# pilly.net
KiCad netlist of a schematic drawn in EAGLE
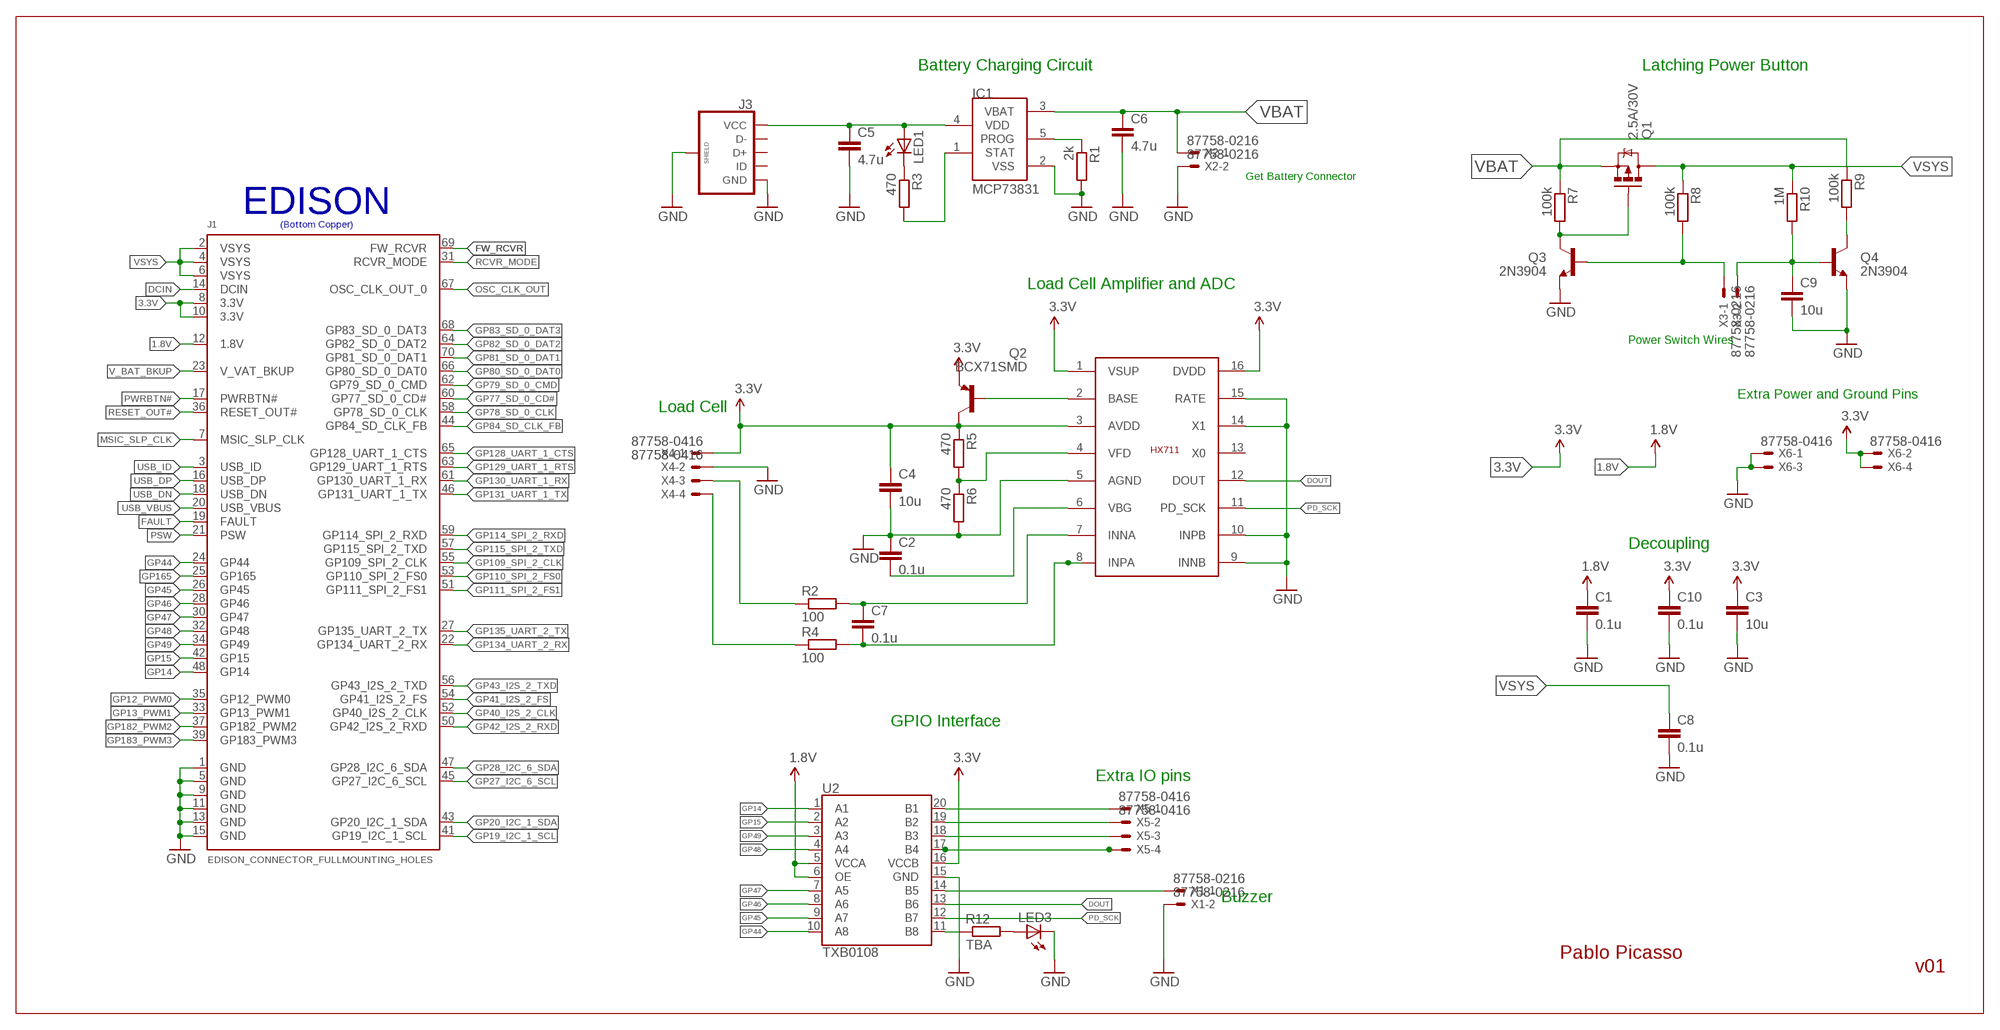
[diagram p0: schematic, sheet 1]

(export (version "E")
  (design (tool "Eeschema 10.0.6"))
  (components
    (comp (ref "C1")
      (value "0.1u")
      (footprint "eagle-import:C0805K")
      (libsource (lib "eagle-import") (part "C-EUC0805K"))
    )
    (comp (ref "C2")
      (value "0.1u")
      (footprint "eagle-import:C0805K")
      (libsource (lib "eagle-import") (part "C-EUC0805K"))
    )
    (comp (ref "C3")
      (value "10u")
      (footprint "eagle-import:C0805K")
      (libsource (lib "eagle-import") (part "C-EUC0805K"))
    )
    (comp (ref "C4")
      (value "10u")
      (footprint "eagle-import:C0805K")
      (libsource (lib "eagle-import") (part "C-EUC0805K"))
    )
    (comp (ref "C5")
      (value "4.7u")
      (footprint "eagle-import:C0805K")
      (libsource (lib "eagle-import") (part "C-EUC0805K"))
    )
    (comp (ref "C6")
      (value "4.7u")
      (footprint "eagle-import:C0805K")
      (libsource (lib "eagle-import") (part "C-EUC0805K"))
    )
    (comp (ref "C7")
      (value "0.1u")
      (footprint "eagle-import:C0805K")
      (libsource (lib "eagle-import") (part "C-EUC0805K"))
    )
    (comp (ref "C8")
      (value "0.1u")
      (footprint "eagle-import:C0805K")
      (libsource (lib "eagle-import") (part "C-EUC0805K"))
    )
    (comp (ref "C9")
      (value "10u")
      (footprint "eagle-import:C0805K")
      (libsource (lib "eagle-import") (part "C-EUC0805K"))
    )
    (comp (ref "C10")
      (value "0.1u")
      (footprint "eagle-import:C0805K")
      (libsource (lib "eagle-import") (part "C-EUC0805K"))
    )
    (comp (ref "IC1")
      (value "MCP73831")
      (footprint "eagle-import:SOT23-5L")
      (libsource (lib "eagle-import") (part "MCP73831"))
    )
    (comp (ref "J1")
      (value "EDISON_CONNECTOR_FULLMOUNTING_HOLES")
      (footprint "eagle-import:EDISON_DAUGHTER")
      (libsource (lib "eagle-import") (part "EDISON_CONNECTOR_FULLMOUNTING_HOLES"))
    )
    (comp (ref "J3")
      (value "USB_MICROB_PLUGCONN-11752")
      (footprint "eagle-import:USB-B-MICRO-SMD_V03")
      (libsource (lib "eagle-import") (part "USB_MICROB_PLUGCONN-11752"))
    )
    (comp (ref "LED1")
      (value "LEDCHIPLED_0805")
      (footprint "eagle-import:CHIPLED_0805")
      (libsource (lib "eagle-import") (part "LEDCHIPLED_0805"))
    )
    (comp (ref "LED3")
      (value "LEDCHIPLED_0805")
      (footprint "eagle-import:CHIPLED_0805")
      (libsource (lib "eagle-import") (part "LEDCHIPLED_0805"))
    )
    (comp (ref "Q1")
      (value "2.5A/30V")
      (footprint "eagle-import:SOT23-3")
      (libsource (lib "eagle-import") (part "MOSFET-PCHANNELDMG2307L"))
    )
    (comp (ref "Q2")
      (value "BCX71SMD")
      (footprint "eagle-import:SOT23")
      (libsource (lib "eagle-import") (part "BCX71SMD"))
    )
    (comp (ref "Q3")
      (value "2N3904")
      (footprint "eagle-import:SOT23-3")
      (libsource (lib "eagle-import") (part "TRANSISTOR_NPNMMBT2222A"))
    )
    (comp (ref "Q4")
      (value "2N3904")
      (footprint "eagle-import:SOT23-3")
      (libsource (lib "eagle-import") (part "TRANSISTOR_NPNMMBT2222A"))
    )
    (comp (ref "R1")
      (value "2k")
      (footprint "eagle-import:R0603")
      (libsource (lib "eagle-import") (part "R-EU_R0603"))
    )
    (comp (ref "R2")
      (value "100")
      (footprint "eagle-import:R0603")
      (libsource (lib "eagle-import") (part "R-EU_R0603"))
    )
    (comp (ref "R3")
      (value "470")
      (footprint "eagle-import:R0603")
      (libsource (lib "eagle-import") (part "R-EU_R0603"))
    )
    (comp (ref "R4")
      (value "100")
      (footprint "eagle-import:R0603")
      (libsource (lib "eagle-import") (part "R-EU_R0603"))
    )
    (comp (ref "R5")
      (value "470")
      (footprint "eagle-import:R0603")
      (libsource (lib "eagle-import") (part "R-EU_R0603"))
    )
    (comp (ref "R6")
      (value "470")
      (footprint "eagle-import:R0603")
      (libsource (lib "eagle-import") (part "R-EU_R0603"))
    )
    (comp (ref "R7")
      (value "100k")
      (footprint "eagle-import:R0603")
      (libsource (lib "eagle-import") (part "R-EU_R0603"))
    )
    (comp (ref "R8")
      (value "100k")
      (footprint "eagle-import:R0603")
      (libsource (lib "eagle-import") (part "R-EU_R0603"))
    )
    (comp (ref "R9")
      (value "100k")
      (footprint "eagle-import:R0603")
      (libsource (lib "eagle-import") (part "R-EU_R0603"))
    )
    (comp (ref "R10")
      (value "1M")
      (footprint "eagle-import:R0603")
      (libsource (lib "eagle-import") (part "R-EU_R0603"))
    )
    (comp (ref "R12")
      (value "TBA")
      (footprint "eagle-import:R0603")
      (libsource (lib "eagle-import") (part "R-EU_R0603"))
    )
    (comp (ref "U$1")
      (value "HX711")
      (footprint "eagle-import:SO16")
      (libsource (lib "eagle-import") (part "HX711"))
    )
    (comp (ref "U2")
      (value "TXB0108")
      (footprint "eagle-import:UFDFN-20")
      (libsource (lib "eagle-import") (part "TXB0108"))
    )
    (comp (ref "X1")
      (value "87758-0216")
      (footprint "eagle-import:87758-0216")
      (libsource (lib "eagle-import") (part "87758-0216"))
    )
    (comp (ref "X2")
      (value "87758-0216")
      (footprint "eagle-import:87758-0216")
      (libsource (lib "eagle-import") (part "87758-0216"))
    )
    (comp (ref "X3")
      (value "87758-0216")
      (footprint "eagle-import:87758-0216")
      (libsource (lib "eagle-import") (part "87758-0216"))
    )
    (comp (ref "X4")
      (value "87758-0416")
      (footprint "eagle-import:87758-0416")
      (fields (field (name "MF") "FARNELL"))
      (libsource (lib "eagle-import") (part "87758-0416"))
    )
    (comp (ref "X5")
      (value "87758-0416")
      (footprint "eagle-import:87758-0416")
      (fields (field (name "MF") "FARNELL"))
      (libsource (lib "eagle-import") (part "87758-0416"))
    )
    (comp (ref "X6")
      (value "87758-0416")
      (footprint "eagle-import:87758-0416")
      (fields (field (name "MF") "FARNELL"))
      (libsource (lib "eagle-import") (part "87758-0416"))
    )
  )
  (nets
    (net (code "1") (name "1.8V") (class "Default")
      (node (ref "C1") (pin "1") (pinfunction "1_1") (pintype "passive"))
      (node (ref "J1") (pin "12") (pinfunction "1.8V_12") (pintype "bidirectional"))
      (node (ref "U2") (pin "5") (pinfunction "VCCA_5") (pintype "bidirectional"))
      (node (ref "U2") (pin "6") (pinfunction "OE_6") (pintype "bidirectional"))
    )
    (net (code "2") (name "3.3V") (class "Default")
      (node (ref "C10") (pin "1") (pinfunction "1_1") (pintype "passive"))
      (node (ref "C3") (pin "1") (pinfunction "1_1") (pintype "passive"))
      (node (ref "C4") (pin "1") (pinfunction "1_1") (pintype "passive"))
      (node (ref "J1") (pin "10") (pinfunction "3.3V_10") (pintype "bidirectional"))
      (node (ref "J1") (pin "8") (pinfunction "3.3V_8") (pintype "bidirectional"))
      (node (ref "Q2") (pin "2") (pinfunction "E_2") (pintype "passive"))
      (node (ref "Q2") (pin "3") (pinfunction "C_3") (pintype "passive"))
      (node (ref "R5") (pin "1") (pinfunction "1_1") (pintype "passive"))
      (node (ref "U$1") (pin "1") (pinfunction "VSUP_1") (pintype "bidirectional"))
      (node (ref "U$1") (pin "16") (pinfunction "DVDD_16") (pintype "bidirectional"))
      (node (ref "U$1") (pin "3") (pinfunction "AVDD_3") (pintype "bidirectional"))
      (node (ref "U2") (pin "16") (pinfunction "VCCB_16") (pintype "bidirectional"))
      (node (ref "X4") (pin "1") (pinfunction "S_1") (pintype "passive"))
      (node (ref "X6") (pin "2") (pinfunction "S_2") (pintype "passive"))
      (node (ref "X6") (pin "4") (pinfunction "S_4") (pintype "passive"))
    )
    (net (code "3") (name "DCIN") (class "Default")
      (node (ref "J1") (pin "14") (pinfunction "DCIN_14") (pintype "bidirectional"))
    )
    (net (code "4") (name "DOUT") (class "Default")
      (node (ref "U$1") (pin "12") (pinfunction "DOUT_12") (pintype "bidirectional"))
      (node (ref "U2") (pin "13") (pinfunction "B6_13") (pintype "bidirectional"))
    )
    (net (code "5") (name "FAULT") (class "Default")
      (node (ref "J1") (pin "19") (pinfunction "FAULT_19") (pintype "bidirectional"))
    )
    (net (code "6") (name "FW_RCVR") (class "Default")
      (node (ref "J1") (pin "69") (pinfunction "FW_RCVR_69") (pintype "bidirectional"))
    )
    (net (code "7") (name "GND") (class "Default")
      (node (ref "C1") (pin "2") (pinfunction "2_2") (pintype "passive"))
      (node (ref "C10") (pin "2") (pinfunction "2_2") (pintype "passive"))
      (node (ref "C2") (pin "1") (pinfunction "1_1") (pintype "passive"))
      (node (ref "C3") (pin "2") (pinfunction "2_2") (pintype "passive"))
      (node (ref "C4") (pin "2") (pinfunction "2_2") (pintype "passive"))
      (node (ref "C5") (pin "2") (pinfunction "2_2") (pintype "passive"))
      (node (ref "C6") (pin "2") (pinfunction "2_2") (pintype "passive"))
      (node (ref "C8") (pin "2") (pinfunction "2_2") (pintype "passive"))
      (node (ref "C9") (pin "2") (pinfunction "2_2") (pintype "passive"))
      (node (ref "IC1") (pin "2") (pinfunction "VSS_2") (pintype "bidirectional"))
      (node (ref "J1") (pin "1") (pinfunction "GND_1") (pintype "bidirectional"))
      (node (ref "J1") (pin "11") (pinfunction "GND_11") (pintype "bidirectional"))
      (node (ref "J1") (pin "13") (pinfunction "GND_13") (pintype "bidirectional"))
      (node (ref "J1") (pin "15") (pinfunction "GND_15") (pintype "bidirectional"))
      (node (ref "J1") (pin "5") (pinfunction "GND_5") (pintype "bidirectional"))
      (node (ref "J1") (pin "9") (pinfunction "GND_9") (pintype "bidirectional"))
      (node (ref "J3") (pin "GND") (pinfunction "GND_GND") (pintype "bidirectional"))
      (node (ref "J3") (pin "SHIELD1") (pinfunction "SHIELD_SHIELD1") (pintype "bidirectional"))
      (node (ref "J3") (pin "SHIELD2") (pinfunction "SHIELD_SHIELD2") (pintype "bidirectional"))
      (node (ref "J3") (pin "SHIELD3") (pinfunction "SHIELD_SHIELD3") (pintype "bidirectional"))
      (node (ref "LED3") (pin "C") (pinfunction "C_C") (pintype "passive"))
      (node (ref "Q3") (pin "2") (pinfunction "E_2") (pintype "passive"))
      (node (ref "Q4") (pin "2") (pinfunction "E_2") (pintype "passive"))
      (node (ref "R1") (pin "2") (pinfunction "2_2") (pintype "passive"))
      (node (ref "R6") (pin "2") (pinfunction "2_2") (pintype "passive"))
      (node (ref "U$1") (pin "10") (pinfunction "INPB_10") (pintype "bidirectional"))
      (node (ref "U$1") (pin "14") (pinfunction "X1_14") (pintype "bidirectional"))
      (node (ref "U$1") (pin "15") (pinfunction "RATE_15") (pintype "bidirectional"))
      (node (ref "U$1") (pin "5") (pinfunction "AGND_5") (pintype "bidirectional"))
      (node (ref "U$1") (pin "9") (pinfunction "INNB_9") (pintype "bidirectional"))
      (node (ref "U2") (pin "15") (pinfunction "GND_15") (pintype "bidirectional"))
      (node (ref "X1") (pin "2") (pinfunction "S_2") (pintype "passive"))
      (node (ref "X2") (pin "2") (pinfunction "S_2") (pintype "passive"))
      (node (ref "X4") (pin "2") (pinfunction "S_2") (pintype "passive"))
      (node (ref "X6") (pin "1") (pinfunction "S_1") (pintype "passive"))
      (node (ref "X6") (pin "3") (pinfunction "S_3") (pintype "passive"))
    )
    (net (code "8") (name "GP12_PWM0") (class "Default")
      (node (ref "J1") (pin "35") (pinfunction "GP12_PWM0_35") (pintype "bidirectional"))
    )
    (net (code "9") (name "GP13_PWM1") (class "Default")
      (node (ref "J1") (pin "33") (pinfunction "GP13_PWM1_33") (pintype "bidirectional"))
    )
    (net (code "10") (name "GP14") (class "Default")
      (node (ref "J1") (pin "48") (pinfunction "GP14_48") (pintype "bidirectional"))
      (node (ref "U2") (pin "1") (pinfunction "A1_1") (pintype "bidirectional"))
    )
    (net (code "11") (name "GP15") (class "Default")
      (node (ref "J1") (pin "42") (pinfunction "GP15_42") (pintype "bidirectional"))
      (node (ref "U2") (pin "2") (pinfunction "A2_2") (pintype "bidirectional"))
    )
    (net (code "12") (name "GP19_I2C_1_SCL") (class "Default")
      (node (ref "J1") (pin "41") (pinfunction "GP19_I2C_1_SCL_41") (pintype "bidirectional"))
    )
    (net (code "13") (name "GP20_I2C_1_SDA") (class "Default")
      (node (ref "J1") (pin "43") (pinfunction "GP20_I2C_1_SDA_43") (pintype "bidirectional"))
    )
    (net (code "14") (name "GP27_I2C_6_SCL") (class "Default")
      (node (ref "J1") (pin "45") (pinfunction "GP27_I2C_6_SCL_45") (pintype "bidirectional"))
    )
    (net (code "15") (name "GP28_I2C_6_SDA") (class "Default")
      (node (ref "J1") (pin "47") (pinfunction "GP28_I2C_6_SDA_47") (pintype "bidirectional"))
    )
    (net (code "16") (name "GP40_I2S_2_CLK") (class "Default")
      (node (ref "J1") (pin "52") (pinfunction "GP40_I2S_2_CLK_52") (pintype "bidirectional"))
    )
    (net (code "17") (name "GP41_I2S_2_FS") (class "Default")
      (node (ref "J1") (pin "54") (pinfunction "GP41_I2S_2_FS_54") (pintype "bidirectional"))
    )
    (net (code "18") (name "GP42_I2S_2_RXD") (class "Default")
      (node (ref "J1") (pin "50") (pinfunction "GP42_I2S_2_RXD_50") (pintype "bidirectional"))
    )
    (net (code "19") (name "GP43_I2S_2_TXD") (class "Default")
      (node (ref "J1") (pin "56") (pinfunction "GP43_I2S_2_TXD_56") (pintype "bidirectional"))
    )
    (net (code "20") (name "GP44") (class "Default")
      (node (ref "J1") (pin "24") (pinfunction "GP44_24") (pintype "bidirectional"))
      (node (ref "U2") (pin "10") (pinfunction "A8_10") (pintype "bidirectional"))
    )
    (net (code "21") (name "GP45") (class "Default")
      (node (ref "J1") (pin "26") (pinfunction "GP45_26") (pintype "bidirectional"))
      (node (ref "U2") (pin "9") (pinfunction "A7_9") (pintype "bidirectional"))
    )
    (net (code "22") (name "GP46") (class "Default")
      (node (ref "J1") (pin "28") (pinfunction "GP46_28") (pintype "bidirectional"))
      (node (ref "U2") (pin "8") (pinfunction "A6_8") (pintype "bidirectional"))
    )
    (net (code "23") (name "GP47") (class "Default")
      (node (ref "J1") (pin "30") (pinfunction "GP47_30") (pintype "bidirectional"))
      (node (ref "U2") (pin "7") (pinfunction "A5_7") (pintype "bidirectional"))
    )
    (net (code "24") (name "GP48") (class "Default")
      (node (ref "J1") (pin "32") (pinfunction "GP48_32") (pintype "bidirectional"))
      (node (ref "U2") (pin "4") (pinfunction "A4_4") (pintype "bidirectional"))
    )
    (net (code "25") (name "GP49") (class "Default")
      (node (ref "J1") (pin "34") (pinfunction "GP49_34") (pintype "bidirectional"))
      (node (ref "U2") (pin "3") (pinfunction "A3_3") (pintype "bidirectional"))
    )
    (net (code "26") (name "GP77_SD_0_CD#") (class "Default")
      (node (ref "J1") (pin "60") (pinfunction "GP77_SD_0_CD#_60") (pintype "bidirectional"))
    )
    (net (code "27") (name "GP78_SD_0_CLK") (class "Default")
      (node (ref "J1") (pin "58") (pinfunction "GP78_SD_0_CLK_58") (pintype "bidirectional"))
    )
    (net (code "28") (name "GP79_SD_0_CMD") (class "Default")
      (node (ref "J1") (pin "62") (pinfunction "GP79_SD_0_CMD_62") (pintype "bidirectional"))
    )
    (net (code "29") (name "GP80_SD_0_DAT0") (class "Default")
      (node (ref "J1") (pin "66") (pinfunction "GP80_SD_0_DAT0_66") (pintype "bidirectional"))
    )
    (net (code "30") (name "GP81_SD_0_DAT1") (class "Default")
      (node (ref "J1") (pin "70") (pinfunction "GP81_SD_0_DAT1_70") (pintype "bidirectional"))
    )
    (net (code "31") (name "GP82_SD_0_DAT2") (class "Default")
      (node (ref "J1") (pin "64") (pinfunction "GP82_SD_0_DAT2_64") (pintype "bidirectional"))
    )
    (net (code "32") (name "GP83_SD_0_DAT3") (class "Default")
      (node (ref "J1") (pin "68") (pinfunction "GP83_SD_0_DAT3_68") (pintype "bidirectional"))
    )
    (net (code "33") (name "GP84_SD_CLK_FB") (class "Default")
      (node (ref "J1") (pin "44") (pinfunction "GP84_SD_CLK_FB_44") (pintype "bidirectional"))
    )
    (net (code "34") (name "GP109_SPI_2_CLK") (class "Default")
      (node (ref "J1") (pin "55") (pinfunction "GP109_SPI_2_CLK_55") (pintype "bidirectional"))
    )
    (net (code "35") (name "GP110_SPI_2_FS0") (class "Default")
      (node (ref "J1") (pin "53") (pinfunction "GP110_SPI_2_FS0_53") (pintype "bidirectional"))
    )
    (net (code "36") (name "GP111_SPI_2_FS1") (class "Default")
      (node (ref "J1") (pin "51") (pinfunction "GP111_SPI_2_FS1_51") (pintype "bidirectional"))
    )
    (net (code "37") (name "GP114_SPI_2_RXD") (class "Default")
      (node (ref "J1") (pin "59") (pinfunction "GP114_SPI_2_RXD_59") (pintype "bidirectional"))
    )
    (net (code "38") (name "GP115_SPI_2_TXD") (class "Default")
      (node (ref "J1") (pin "57") (pinfunction "GP115_SPI_2_TXD_57") (pintype "bidirectional"))
    )
    (net (code "39") (name "GP128_UART_1_CTS") (class "Default")
      (node (ref "J1") (pin "65") (pinfunction "GP128_UART_1_CTS_65") (pintype "bidirectional"))
    )
    (net (code "40") (name "GP129_UART_1_RTS") (class "Default")
      (node (ref "J1") (pin "63") (pinfunction "GP129_UART_1_RTS_63") (pintype "bidirectional"))
    )
    (net (code "41") (name "GP130_UART_1_RX") (class "Default")
      (node (ref "J1") (pin "61") (pinfunction "GP130_UART_1_RX_61") (pintype "bidirectional"))
    )
    (net (code "42") (name "GP131_UART_1_TX") (class "Default")
      (node (ref "J1") (pin "46") (pinfunction "GP131_UART_1_TX_46") (pintype "bidirectional"))
    )
    (net (code "43") (name "GP134_UART_2_RX") (class "Default")
      (node (ref "J1") (pin "22") (pinfunction "GP134_UART_2_RX_22") (pintype "bidirectional"))
    )
    (net (code "44") (name "GP135_UART_2_TX") (class "Default")
      (node (ref "J1") (pin "27") (pinfunction "GP135_UART_2_TX_27") (pintype "bidirectional"))
    )
    (net (code "45") (name "GP165") (class "Default")
      (node (ref "J1") (pin "25") (pinfunction "GP165_25") (pintype "bidirectional"))
    )
    (net (code "46") (name "GP182_PWM2") (class "Default")
      (node (ref "J1") (pin "37") (pinfunction "GP182_PWM2_37") (pintype "bidirectional"))
    )
    (net (code "47") (name "GP183_PWM3") (class "Default")
      (node (ref "J1") (pin "39") (pinfunction "GP183_PWM3_39") (pintype "bidirectional"))
    )
    (net (code "48") (name "MSIC_SLP_CLK") (class "Default")
      (node (ref "J1") (pin "7") (pinfunction "MSIC_SLP_CLK_7") (pintype "bidirectional"))
    )
    (net (code "49") (name "Net-(IC1-PROG)") (class "Default")
      (node (ref "IC1") (pin "5") (pinfunction "PROG_5") (pintype "bidirectional"))
      (node (ref "R1") (pin "1") (pinfunction "1_1") (pintype "passive"))
    )
    (net (code "50") (name "Net-(IC1-STAT)") (class "Default")
      (node (ref "IC1") (pin "1") (pinfunction "STAT_1") (pintype "bidirectional"))
      (node (ref "R3") (pin "2") (pinfunction "2_2") (pintype "passive"))
    )
    (net (code "51") (name "Net-(IC1-VDD)") (class "Default")
      (node (ref "C5") (pin "1") (pinfunction "1_1") (pintype "passive"))
      (node (ref "IC1") (pin "4") (pinfunction "VDD_4") (pintype "bidirectional"))
      (node (ref "J3") (pin "VBUS") (pinfunction "VCC_VBUS") (pintype "bidirectional"))
      (node (ref "LED1") (pin "A") (pinfunction "A_A") (pintype "passive"))
    )
    (net (code "52") (name "Net-(LED1-PadC)") (class "Default")
      (node (ref "LED1") (pin "C") (pinfunction "C_C") (pintype "passive"))
      (node (ref "R3") (pin "1") (pinfunction "1_1") (pintype "passive"))
    )
    (net (code "53") (name "Net-(LED3-PadA)") (class "Default")
      (node (ref "LED3") (pin "A") (pinfunction "A_A") (pintype "passive"))
      (node (ref "R12") (pin "2") (pinfunction "2_2") (pintype "passive"))
    )
    (net (code "54") (name "Net-(Q1-G)") (class "Default")
      (node (ref "Q1") (pin "1") (pinfunction "G_1") (pintype "passive"))
      (node (ref "Q3") (pin "3") (pinfunction "C_3") (pintype "passive"))
      (node (ref "R7") (pin "2") (pinfunction "2_2") (pintype "passive"))
    )
    (net (code "55") (name "Net-(Q2-B)") (class "Default")
      (node (ref "Q2") (pin "1") (pinfunction "B_1") (pintype "passive"))
      (node (ref "U$1") (pin "2") (pinfunction "BASE_2") (pintype "bidirectional"))
    )
    (net (code "56") (name "Net-(Q3-B)") (class "Default")
      (node (ref "Q3") (pin "1") (pinfunction "B_1") (pintype "passive"))
      (node (ref "R8") (pin "2") (pinfunction "2_2") (pintype "passive"))
      (node (ref "X3") (pin "1") (pinfunction "S_1") (pintype "passive"))
    )
    (net (code "57") (name "Net-(Q4-B)") (class "Default")
      (node (ref "C9") (pin "1") (pinfunction "1_1") (pintype "passive"))
      (node (ref "Q4") (pin "1") (pinfunction "B_1") (pintype "passive"))
      (node (ref "R10") (pin "2") (pinfunction "2_2") (pintype "passive"))
      (node (ref "X3") (pin "2") (pinfunction "S_2") (pintype "passive"))
    )
    (net (code "58") (name "Net-(Q4-C)") (class "Default")
      (node (ref "Q4") (pin "3") (pinfunction "C_3") (pintype "passive"))
      (node (ref "R9") (pin "2") (pinfunction "2_2") (pintype "passive"))
    )
    (net (code "59") (name "Net-(U$1-INNA)") (class "Default")
      (node (ref "C7") (pin "1") (pinfunction "1_1") (pintype "passive"))
      (node (ref "R2") (pin "2") (pinfunction "2_2") (pintype "passive"))
      (node (ref "U$1") (pin "7") (pinfunction "INNA_7") (pintype "bidirectional"))
    )
    (net (code "60") (name "Net-(U$1-INPA)") (class "Default")
      (node (ref "C7") (pin "2") (pinfunction "2_2") (pintype "passive"))
      (node (ref "R4") (pin "2") (pinfunction "2_2") (pintype "passive"))
      (node (ref "U$1") (pin "8") (pinfunction "INPA_8") (pintype "bidirectional"))
    )
    (net (code "61") (name "Net-(U$1-VBG)") (class "Default")
      (node (ref "C2") (pin "2") (pinfunction "2_2") (pintype "passive"))
      (node (ref "U$1") (pin "6") (pinfunction "VBG_6") (pintype "bidirectional"))
    )
    (net (code "62") (name "Net-(U$1-VFD)") (class "Default")
      (node (ref "R5") (pin "2") (pinfunction "2_2") (pintype "passive"))
      (node (ref "R6") (pin "1") (pinfunction "1_1") (pintype "passive"))
      (node (ref "U$1") (pin "4") (pinfunction "VFD_4") (pintype "bidirectional"))
    )
    (net (code "63") (name "Net-(U2-B1)") (class "Default")
      (node (ref "U2") (pin "20") (pinfunction "B1_20") (pintype "bidirectional"))
      (node (ref "X5") (pin "1") (pinfunction "S_1") (pintype "passive"))
    )
    (net (code "64") (name "Net-(U2-B2)") (class "Default")
      (node (ref "U2") (pin "19") (pinfunction "B2_19") (pintype "bidirectional"))
      (node (ref "X5") (pin "2") (pinfunction "S_2") (pintype "passive"))
    )
    (net (code "65") (name "Net-(U2-B3)") (class "Default")
      (node (ref "U2") (pin "18") (pinfunction "B3_18") (pintype "bidirectional"))
      (node (ref "X5") (pin "3") (pinfunction "S_3") (pintype "passive"))
    )
    (net (code "66") (name "Net-(U2-B4)") (class "Default")
      (node (ref "U2") (pin "17") (pinfunction "B4_17") (pintype "bidirectional"))
      (node (ref "X5") (pin "4") (pinfunction "S_4") (pintype "passive"))
    )
    (net (code "67") (name "Net-(U2-B5)") (class "Default")
      (node (ref "U2") (pin "14") (pinfunction "B5_14") (pintype "bidirectional"))
      (node (ref "X1") (pin "1") (pinfunction "S_1") (pintype "passive"))
    )
    (net (code "68") (name "Net-(U2-B8)") (class "Default")
      (node (ref "R12") (pin "1") (pinfunction "1_1") (pintype "passive"))
      (node (ref "U2") (pin "11") (pinfunction "B8_11") (pintype "bidirectional"))
    )
    (net (code "69") (name "Net-(X4C-S)") (class "Default")
      (node (ref "R2") (pin "1") (pinfunction "1_1") (pintype "passive"))
      (node (ref "X4") (pin "3") (pinfunction "S_3") (pintype "passive"))
    )
    (net (code "70") (name "Net-(X4D-S)") (class "Default")
      (node (ref "R4") (pin "1") (pinfunction "1_1") (pintype "passive"))
      (node (ref "X4") (pin "4") (pinfunction "S_4") (pintype "passive"))
    )
    (net (code "71") (name "OSC_CLK_OUT") (class "Default")
      (node (ref "J1") (pin "67") (pinfunction "OSC_CLK_OUT_0_67") (pintype "bidirectional"))
    )
    (net (code "72") (name "PD_SCK") (class "Default")
      (node (ref "U$1") (pin "11") (pinfunction "PD_SCK_11") (pintype "bidirectional"))
      (node (ref "U2") (pin "12") (pinfunction "B7_12") (pintype "bidirectional"))
    )
    (net (code "73") (name "PSW") (class "Default")
      (node (ref "J1") (pin "21") (pinfunction "PSW_21") (pintype "bidirectional"))
    )
    (net (code "74") (name "PWRBTN#") (class "Default")
      (node (ref "J1") (pin "17") (pinfunction "PWRBTN#_17") (pintype "bidirectional"))
    )
    (net (code "75") (name "RCVR_MODE") (class "Default")
      (node (ref "J1") (pin "31") (pinfunction "RCVR_MODE_31") (pintype "bidirectional"))
    )
    (net (code "76") (name "RESET_OUT#") (class "Default")
      (node (ref "J1") (pin "36") (pinfunction "RESET_OUT#_36") (pintype "bidirectional"))
    )
    (net (code "77") (name "USB_DN") (class "Default")
      (node (ref "J1") (pin "18") (pinfunction "USB_DN_18") (pintype "bidirectional"))
    )
    (net (code "78") (name "USB_DP") (class "Default")
      (node (ref "J1") (pin "16") (pinfunction "USB_DP_16") (pintype "bidirectional"))
    )
    (net (code "79") (name "USB_ID") (class "Default")
      (node (ref "J1") (pin "3") (pinfunction "USB_ID_3") (pintype "bidirectional"))
    )
    (net (code "80") (name "USB_VBUS") (class "Default")
      (node (ref "J1") (pin "20") (pinfunction "USB_VBUS_20") (pintype "bidirectional"))
    )
    (net (code "81") (name "VBAT") (class "Default")
      (node (ref "C6") (pin "1") (pinfunction "1_1") (pintype "passive"))
      (node (ref "IC1") (pin "3") (pinfunction "VBAT_3") (pintype "bidirectional"))
      (node (ref "Q1") (pin "2") (pinfunction "S_2") (pintype "passive"))
      (node (ref "R7") (pin "1") (pinfunction "1_1") (pintype "passive"))
      (node (ref "R9") (pin "1") (pinfunction "1_1") (pintype "passive"))
      (node (ref "X2") (pin "1") (pinfunction "S_1") (pintype "passive"))
    )
    (net (code "82") (name "VSYS") (class "Default")
      (node (ref "C8") (pin "1") (pinfunction "1_1") (pintype "passive"))
      (node (ref "J1") (pin "2") (pinfunction "VSYS_2") (pintype "bidirectional"))
      (node (ref "J1") (pin "4") (pinfunction "VSYS_4") (pintype "bidirectional"))
      (node (ref "J1") (pin "6") (pinfunction "VSYS_6") (pintype "bidirectional"))
      (node (ref "Q1") (pin "3") (pinfunction "D_3") (pintype "passive"))
      (node (ref "R10") (pin "1") (pinfunction "1_1") (pintype "passive"))
      (node (ref "R8") (pin "1") (pinfunction "1_1") (pintype "passive"))
    )
    (net (code "83") (name "V_BAT_BKUP") (class "Default")
      (node (ref "J1") (pin "23") (pinfunction "V_VAT_BKUP_23") (pintype "bidirectional"))
    )
    (net (code "84") (name "unconnected-(J3-PadD+)") (class "Default")
      (node (ref "J3") (pin "D+") (pinfunction "D+_D+") (pintype "bidirectional"))
    )
    (net (code "85") (name "unconnected-(J3-PadD-)") (class "Default")
      (node (ref "J3") (pin "D-") (pinfunction "D-_D-") (pintype "bidirectional"))
    )
    (net (code "86") (name "unconnected-(J3-PadID)") (class "Default")
      (node (ref "J3") (pin "ID") (pinfunction "ID_ID") (pintype "bidirectional"))
    )
    (net (code "87") (name "unconnected-(U$1-X0-Pad13)") (class "Default")
      (node (ref "U$1") (pin "13") (pinfunction "X0_13") (pintype "bidirectional"))
    )
  )
)
